# SUBBOARD-EMC_input.net
KiCad netlist of a schematic drawn in Altium Designer
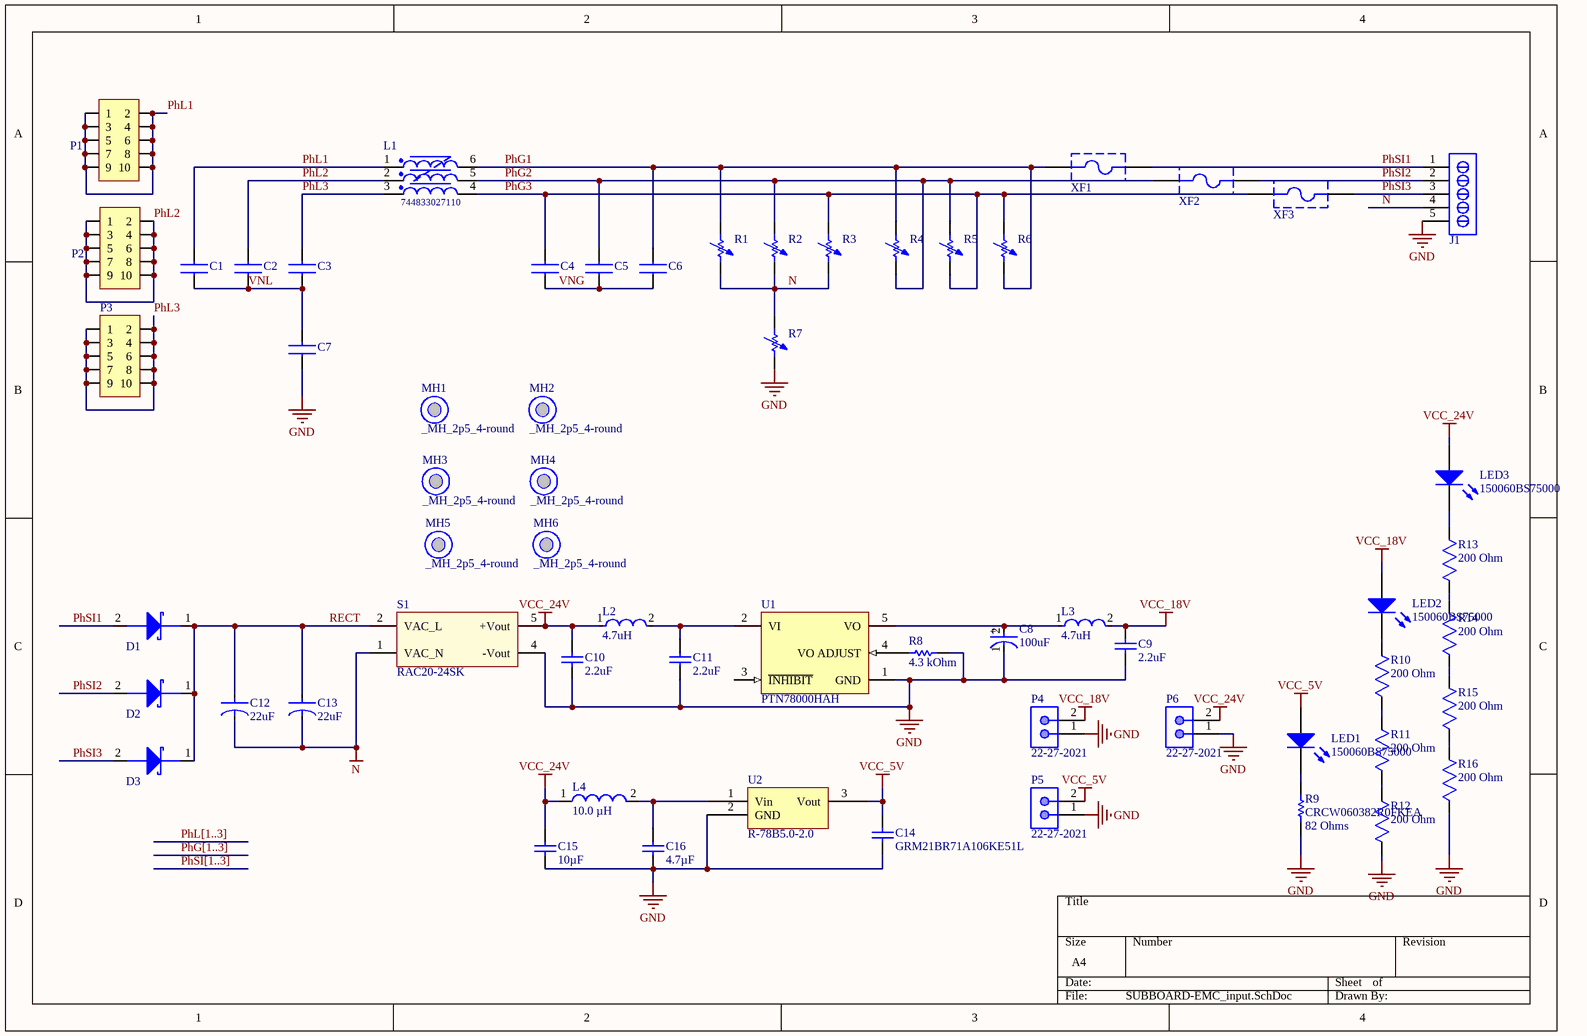
[diagram p0: SUBBOARD-EMC_input.SchDoc]

(export (version "E")
  (design (tool "Eeschema 10.0.6"))
  (components
    (comp (ref "C1")
      (value "PHE840MZ7100MF11R06L2")
      (footprint "PHE840MZ7100MF11R06L2")
      (description "CAP FILM 1UF 20% 760VDC RADIAL")
      (fields (field (name "MANUFACTURER") "KEMET") (field (name "TOLERANCE") "20%"))
      (libsource (lib "Altium_Library_POWERLAB") (part "PHE840MZ7100MF11R06L2"))
    )
    (comp (ref "C2")
      (value "PHE840MZ7100MF11R06L2")
      (footprint "PHE840MZ7100MF11R06L2")
      (description "CAP FILM 1UF 20% 760VDC RADIAL")
      (fields (field (name "MANUFACTURER") "KEMET") (field (name "TOLERANCE") "20%"))
      (libsource (lib "Altium_Library_POWERLAB") (part "PHE840MZ7100MF11R06L2"))
    )
    (comp (ref "C3")
      (value "PHE840MZ7100MF11R06L2")
      (footprint "PHE840MZ7100MF11R06L2")
      (description "CAP FILM 1UF 20% 760VDC RADIAL")
      (fields (field (name "MANUFACTURER") "KEMET") (field (name "TOLERANCE") "20%"))
      (libsource (lib "Altium_Library_POWERLAB") (part "PHE840MZ7100MF11R06L2"))
    )
    (comp (ref "C4")
      (value "PHE840MZ7100MF11R06L2")
      (footprint "PHE840MZ7100MF11R06L2")
      (description "CAP FILM 1UF 20% 760VDC RADIAL")
      (fields (field (name "MANUFACTURER") "KEMET") (field (name "TOLERANCE") "20%"))
      (libsource (lib "Altium_Library_POWERLAB") (part "PHE840MZ7100MF11R06L2"))
    )
    (comp (ref "C5")
      (value "PHE840MZ7100MF11R06L2")
      (footprint "PHE840MZ7100MF11R06L2")
      (description "CAP FILM 1UF 20% 760VDC RADIAL")
      (fields (field (name "MANUFACTURER") "KEMET") (field (name "TOLERANCE") "20%"))
      (libsource (lib "Altium_Library_POWERLAB") (part "PHE840MZ7100MF11R06L2"))
    )
    (comp (ref "C6")
      (value "PHE840MZ7100MF11R06L2")
      (footprint "PHE840MZ7100MF11R06L2")
      (description "CAP FILM 1UF 20% 760VDC RADIAL")
      (fields (field (name "MANUFACTURER") "KEMET") (field (name "TOLERANCE") "20%"))
      (libsource (lib "Altium_Library_POWERLAB") (part "PHE840MZ7100MF11R06L2"))
    )
    (comp (ref "C7")
      (value "PHE850ER7100MR03R06L2")
      (footprint "PHE850ER7100MR03R06L2")
      (description "CAP FILM 1UF 20% 1.25KVDC RADIAL")
      (fields (field (name "MANUFACTURER") "KEMET") (field (name "TOLERANCE") "20%"))
      (libsource (lib "Altium_Library_POWERLAB") (part "PHE850ER7100MR03R06L2"))
    )
    (comp (ref "C8")
      (value "EEE-FK1H101P")
      (footprint "FP-EEE-FK1H101P-MFG")
      (description "CAP ALUM 100UF 20% 50V SMD")
      (fields
        (field (name "TOLERANCE") "20%")
        (field (name "OCTOPART") "https://octopart.com/eeefk1h101p-panasonic-4642841")
        (field (name "CAPACITANCE") "100uF")
      )
      (libsource (lib "Altium Content Vault") (part "cf48714ba7e38822c1575c7ec0b6d1f"))
    )
    (comp (ref "C9")
      (value "C1210C225K5RACTU")
      (footprint "CAPC3225X140X50ML20T25")
      (description "Chip Capacitor, 2.2 uF, +/- 10%, 50 V, -55 to 125 degC, 1210 (3225 Metric), RoHS, Tape and Reel")
      (fields
        (field (name "MANUFACTURER") "Kemet")
        (field (name "CAPACITANCE") "2.2uF")
        (field (name "TOLERANCE") "10%")
      )
      (libsource (lib "Altium Content Vault") (part "CAP-NP-2"))
    )
    (comp (ref "C10")
      (value "C1210C225K5RACTU")
      (footprint "CAPC3225X140X50ML20T25")
      (description "Chip Capacitor, 2.2 uF, +/- 10%, 50 V, -55 to 125 degC, 1210 (3225 Metric), RoHS, Tape and Reel")
      (fields
        (field (name "MANUFACTURER") "Kemet")
        (field (name "CAPACITANCE") "2.2uF")
        (field (name "TOLERANCE") "10%")
      )
      (libsource (lib "Altium Content Vault") (part "CAP-NP-2"))
    )
    (comp (ref "C11")
      (value "C1210C225K5RACTU")
      (footprint "CAPC3225X140X50ML20T25")
      (description "Chip Capacitor, 2.2 uF, +/- 10%, 50 V, -55 to 125 degC, 1210 (3225 Metric), RoHS, Tape and Reel")
      (fields
        (field (name "MANUFACTURER") "Kemet")
        (field (name "CAPACITANCE") "2.2uF")
        (field (name "TOLERANCE") "10%")
      )
      (libsource (lib "Altium Content Vault") (part "CAP-NP-2"))
    )
    (comp (ref "C12")
      (value "EEV-EB2W220M")
      (footprint "EEV-EB2W220M")
      (description "CAP, ALU ELEC, 22UF, 450V, SMD")
      (fields
        (field (name "MANUFACTURER") "Panasonic")
        (field (name "CAPACITANCE") "22uF")
        (field (name "TOLERANCE") "20%")
      )
      (libsource (lib "Altium_Library_POWERLAB") (part "EEV-EB2W220M"))
    )
    (comp (ref "C13")
      (value "EEV-EB2W220M")
      (footprint "EEV-EB2W220M")
      (description "CAP, ALU ELEC, 22UF, 450V, SMD")
      (fields
        (field (name "MANUFACTURER") "Panasonic")
        (field (name "CAPACITANCE") "22uF")
        (field (name "TOLERANCE") "20%")
      )
      (libsource (lib "Altium_Library_POWERLAB") (part "EEV-EB2W220M"))
    )
    (comp (ref "C14")
      (value "GRM21BR71A106KE51L")
      (footprint "CAPC2013X140X45NL15T25")
      (fields (field (name "MANUFACTURER") "Murata"))
      (libsource (lib "Altium Content Vault") (part "CAP"))
    )
    (comp (ref "C15")
      (value "UMK325BJ106KM-T")
      (footprint "CAPC3225X270X60LL30T30")
      (description "Chip Capacitor, 10 uF, +/- 10%, 50 V, -55 to 85 degC, 1210 (3225 Metric), RoHS, Tape and Reel")
      (fields
        (field (name "TOLERANCE") "±10%")
        (field (name "CAPACITANCE") "10µF")
        (field (name "MANUFACTURER") "Taiyo Yuden")
      )
      (libsource (lib "Altium Content Vault") (part "CAP-NP-2"))
    )
    (comp (ref "C16")
      (value "UMK316AB7475KL-T")
      (footprint "CAPC3216X180X55LL20T30")
      (description "Chip Capacitor, 4.7 uF, +/- 10%, 50 V, -55 to 125 degC, 1206 (3216 Metric), RoHS, Tape and Reel")
      (fields
        (field (name "TOLERANCE") "±10%")
        (field (name "MANUFACTURER") "Taiyo Yuden")
        (field (name "CAPACITANCE") "4.7µF")
      )
      (libsource (lib "Altium Content Vault") (part "CAP-NP-2"))
    )
    (comp (ref "D1")
      (value "BYG23T-M3/TR")
      (footprint "BYG23T-M3/TR")
      (description "DIODE AVALANCHE 1300V 1A DO214AC")
      (fields (field (name "MANUFACTURER") "Vishay Semiconductors"))
      (libsource (lib "Altium_Library_POWERLAB") (part "BYG23T-M3/TR"))
    )
    (comp (ref "D2")
      (value "BYG23T-M3/TR")
      (footprint "BYG23T-M3/TR")
      (description "DIODE AVALANCHE 1300V 1A DO214AC")
      (fields (field (name "MANUFACTURER") "Vishay Semiconductors"))
      (libsource (lib "Altium_Library_POWERLAB") (part "BYG23T-M3/TR"))
    )
    (comp (ref "D3")
      (value "BYG23T-M3/TR")
      (footprint "BYG23T-M3/TR")
      (description "DIODE AVALANCHE 1300V 1A DO214AC")
      (fields (field (name "MANUFACTURER") "Vishay Semiconductors"))
      (libsource (lib "Altium_Library_POWERLAB") (part "BYG23T-M3/TR"))
    )
    (comp (ref "J1")
      (value "1715750")
      (footprint "SHDR5W110P0X500_1X5_2532X980X1380P")
      (description "Phoenix Contact MKDS 1.5/ 5-5.08, 5 Way PCB Terminal Block")
      (fields (field (name "MANUFACTURER") "Phoenix Contact") (field (name "VOLTAGE") "300V"))
      (libsource (lib "Altium_Library_POWERLAB") (part "1715750"))
    )
    (comp (ref "L1")
      (value "744833027110")
      (footprint "WE-TPB_Type 3XL_744833027110")
      (description "WE-TPB Common Mode Power Line Choke, Type 3XL, 2.7mH, 11A, 500V")
      (fields (field (name "MANUFACTURER") "Wurth Elektronik"))
      (libsource (lib "Altium_Library_POWERLAB") (part "744833027110"))
    )
    (comp (ref "L2")
      (value "IHLP1616BZER4R7M11")
      (footprint "FP-IHLP-1616BZ-FP_1_8545x-MFG")
      (description "Fixed Inductors Commercial Low DCR Series SMT 4.7uH 1.7A 105mΩ 20%")
      (fields (field (name "INDUCTANCE") "4.7uH") (field (name "TOLERANCE") "20%"))
      (libsource (lib "Altium Content Vault") (part "725321dda6339637d4d059423bc1c3c"))
    )
    (comp (ref "L3")
      (value "IHLP1616BZER4R7M11")
      (footprint "FP-IHLP-1616BZ-FP_1_8545x-MFG")
      (description "Fixed Inductors Commercial Low DCR Series SMT 4.7uH 1.7A 105mΩ 20%")
      (fields (field (name "INDUCTANCE") "4.7uH") (field (name "TOLERANCE") "20%"))
      (libsource (lib "Altium Content Vault") (part "725321dda6339637d4d059423bc1c3c"))
    )
    (comp (ref "L4")
      (value "744777910")
      (footprint "WE-PD-M-PB")
      (description "SMD-Shielded Power Inductor WE-PD, L = 10.0 µH")
      (fields (field (name "INDUCTANCE") "10.0 µH"))
      (libsource (lib "Altium Content Vault") (part "PAS-IND-INDUCTOR-2"))
    )
    (comp (ref "LED1")
      (value "150060BS75000")
      (footprint "0603_A")
      (description "SMD mono-color Chip LED, WL-SMCW, Blue")
      (fields (field (name "MANUFACTURER") "Wuerth Elektronik"))
      (libsource (lib "Altium Content Vault") (part "WE-LED_K1A2-2"))
    )
    (comp (ref "LED2")
      (value "150060BS75000")
      (footprint "0603_A")
      (description "SMD mono-color Chip LED, WL-SMCW, Blue")
      (fields (field (name "MANUFACTURER") "Wuerth Elektronik"))
      (libsource (lib "Altium Content Vault") (part "WE-LED_K1A2-2"))
    )
    (comp (ref "LED3")
      (value "150060BS75000")
      (footprint "0603_A")
      (description "SMD mono-color Chip LED, WL-SMCW, Blue")
      (fields (field (name "MANUFACTURER") "Wuerth Elektronik"))
      (libsource (lib "Altium Content Vault") (part "WE-LED_K1A2-2"))
    )
    (comp (ref "MH1")
      (value "_MH_2p5_4-round")
      (footprint "_MH_2p5_4-round")
      (description "matching hole 2.5 hole, 4mm pad (round)")
      (libsource (lib "Altium_Library_POWERLAB") (part "_MH_2p5_4-round"))
    )
    (comp (ref "MH2")
      (value "_MH_2p5_4-round")
      (footprint "_MH_2p5_4-round")
      (description "matching hole 2.5 hole, 4mm pad (round)")
      (libsource (lib "Altium_Library_POWERLAB") (part "_MH_2p5_4-round"))
    )
    (comp (ref "MH3")
      (value "_MH_2p5_4-round")
      (footprint "_MH_2p5_4-round")
      (description "matching hole 2.5 hole, 4mm pad (round)")
      (libsource (lib "Altium_Library_POWERLAB") (part "_MH_2p5_4-round"))
    )
    (comp (ref "MH4")
      (value "_MH_2p5_4-round")
      (footprint "_MH_2p5_4-round")
      (description "matching hole 2.5 hole, 4mm pad (round)")
      (libsource (lib "Altium_Library_POWERLAB") (part "_MH_2p5_4-round"))
    )
    (comp (ref "MH5")
      (value "_MH_2p5_4-round")
      (footprint "_MH_2p5_4-round")
      (description "matching hole 2.5 hole, 4mm pad (round)")
      (libsource (lib "Altium_Library_POWERLAB") (part "_MH_2p5_4-round"))
    )
    (comp (ref "MH6")
      (value "_MH_2p5_4-round")
      (footprint "_MH_2p5_4-round")
      (description "matching hole 2.5 hole, 4mm pad (round)")
      (libsource (lib "Altium_Library_POWERLAB") (part "_MH_2p5_4-round"))
    )
    (comp (ref "P1")
      (value "IPT1-105-01-S-D-RA")
      (footprint "IPT1-105-01-S-D-RA")
      (description "CONN PLUG .100\" 10POS DL PCB R/A")
      (fields (field (name "MANUFACTURER") "Samtec"))
      (libsource (lib "Altium_Library_POWERLAB") (part "IPT1-105-01-S-D-RA"))
    )
    (comp (ref "P2")
      (value "IPT1-105-01-S-D-RA")
      (footprint "IPT1-105-01-S-D-RA")
      (description "CONN PLUG .100\" 10POS DL PCB R/A")
      (fields (field (name "MANUFACTURER") "Samtec"))
      (libsource (lib "Altium_Library_POWERLAB") (part "IPT1-105-01-S-D-RA"))
    )
    (comp (ref "P3")
      (value "IPT1-105-01-S-D-RA")
      (footprint "IPT1-105-01-S-D-RA")
      (description "CONN PLUG .100\" 10POS DL PCB R/A")
      (fields (field (name "MANUFACTURER") "Samtec"))
      (libsource (lib "Altium_Library_POWERLAB") (part "IPT1-105-01-S-D-RA"))
    )
    (comp (ref "P4")
      (value "22-27-2021")
      (footprint "MOLX-22-27-2021_V")
      (fields (field (name "MANUFACTURER") "Molex") (field (name "PARTNUMBER") "0022272021"))
      (libsource (lib "Altium Content Vault") (part "CN-1P-M-R2"))
    )
    (comp (ref "P5")
      (value "22-27-2021")
      (footprint "MOLX-22-27-2021_V")
      (fields (field (name "MANUFACTURER") "Molex") (field (name "PARTNUMBER") "0022272021"))
      (libsource (lib "Altium Content Vault") (part "CN-1P-M-R2"))
    )
    (comp (ref "P6")
      (value "22-27-2021")
      (footprint "MOLX-22-27-2021_V")
      (fields (field (name "MANUFACTURER") "Molex") (field (name "PARTNUMBER") "0022272021"))
      (libsource (lib "Altium Content Vault") (part "CN-1P-M-R2"))
    )
    (comp (ref "R1")
      (value "VDRS07H300BSE")
      (footprint "VISH-VDRS07-53x22-2_V")
      (fields (field (name "MANUFACTURER") "Vishay Semiconductor"))
      (libsource (lib "Altium Content Vault") (part "VISH-RES_VAR-2"))
    )
    (comp (ref "R2")
      (value "VDRS07H300BSE")
      (footprint "VISH-VDRS07-53x22-2_V")
      (fields (field (name "MANUFACTURER") "Vishay Semiconductor"))
      (libsource (lib "Altium Content Vault") (part "VISH-RES_VAR-2"))
    )
    (comp (ref "R3")
      (value "VDRS07H300BSE")
      (footprint "VISH-VDRS07-53x22-2_V")
      (fields (field (name "MANUFACTURER") "Vishay Semiconductor"))
      (libsource (lib "Altium Content Vault") (part "VISH-RES_VAR-2"))
    )
    (comp (ref "R4")
      (value "VDRS07H300BSE")
      (footprint "VISH-VDRS07-53x22-2_V")
      (fields (field (name "MANUFACTURER") "Vishay Semiconductor"))
      (libsource (lib "Altium Content Vault") (part "VISH-RES_VAR-2"))
    )
    (comp (ref "R5")
      (value "VDRS07H300BSE")
      (footprint "VISH-VDRS07-53x22-2_V")
      (fields (field (name "MANUFACTURER") "Vishay Semiconductor"))
      (libsource (lib "Altium Content Vault") (part "VISH-RES_VAR-2"))
    )
    (comp (ref "R6")
      (value "VDRS07H300BSE")
      (footprint "VISH-VDRS07-53x22-2_V")
      (fields (field (name "MANUFACTURER") "Vishay Semiconductor"))
      (libsource (lib "Altium Content Vault") (part "VISH-RES_VAR-2"))
    )
    (comp (ref "R7")
      (value "VDRS07H300BSE")
      (footprint "VISH-VDRS07-53x22-2_V")
      (fields (field (name "MANUFACTURER") "Vishay Semiconductor"))
      (libsource (lib "Altium Content Vault") (part "VISH-RES_VAR-2"))
    )
    (comp (ref "R8")
      (value "4.3 kOhm")
      (footprint "RESC2013X60X40LL20T25")
      (fields (field (name "MANUFACTURER") "Panasonic") (field (name "PART NUMBER") "ERA6AEB432V"))
      (libsource (lib "Altium Content Vault") (part "RES"))
    )
    (comp (ref "R9")
      (value "CRCW060382R0FKEA")
      (footprint "RESC1609X50X30LL10T20")
      (fields (field (name "MANUFACTURER") "Vishay Dale") (field (name "ALTIUM_VALUE") "82 Ohms"))
      (libsource (lib "Altium Content Vault") (part "RES"))
    )
    (comp (ref "R10")
      (value "200 Ohm")
      (footprint "CRCW0603200RFKEAHP")
      (description "CRCW0603200RFKEAHP\r\nRes Thick Film 0603 200 Ohm 1% 0.25W(1/4W) ±100ppm/C Pad SMD Automotive T/R")
      (fields
        (field (name "MANUFACTURER") "Vishay Dale")
        (field (name "MANUFACTURER PART NUMBER") "CRCW0603200RFKEAHP")
      )
      (libsource (lib "Altium_Library_POWERLAB") (part "CRCW0603200RFKEAHP"))
    )
    (comp (ref "R11")
      (value "200 Ohm")
      (footprint "CRCW0603200RFKEAHP")
      (description "CRCW0603200RFKEAHP\r\nRes Thick Film 0603 200 Ohm 1% 0.25W(1/4W) ±100ppm/C Pad SMD Automotive T/R")
      (fields
        (field (name "MANUFACTURER") "Vishay Dale")
        (field (name "MANUFACTURER PART NUMBER") "CRCW0603200RFKEAHP")
      )
      (libsource (lib "Altium_Library_POWERLAB") (part "CRCW0603200RFKEAHP"))
    )
    (comp (ref "R12")
      (value "200 Ohm")
      (footprint "CRCW0603200RFKEAHP")
      (description "CRCW0603200RFKEAHP\r\nRes Thick Film 0603 200 Ohm 1% 0.25W(1/4W) ±100ppm/C Pad SMD Automotive T/R")
      (fields
        (field (name "MANUFACTURER") "Vishay Dale")
        (field (name "MANUFACTURER PART NUMBER") "CRCW0603200RFKEAHP")
      )
      (libsource (lib "Altium_Library_POWERLAB") (part "CRCW0603200RFKEAHP"))
    )
    (comp (ref "R13")
      (value "200 Ohm")
      (footprint "CRCW0603200RFKEAHP")
      (description "CRCW0603200RFKEAHP\r\nRes Thick Film 0603 200 Ohm 1% 0.25W(1/4W) ±100ppm/C Pad SMD Automotive T/R")
      (fields
        (field (name "MANUFACTURER") "Vishay Dale")
        (field (name "MANUFACTURER PART NUMBER") "CRCW0603200RFKEAHP")
      )
      (libsource (lib "Altium_Library_POWERLAB") (part "CRCW0603200RFKEAHP"))
    )
    (comp (ref "R14")
      (value "200 Ohm")
      (footprint "CRCW0603200RFKEAHP")
      (description "CRCW0603200RFKEAHP\r\nRes Thick Film 0603 200 Ohm 1% 0.25W(1/4W) ±100ppm/C Pad SMD Automotive T/R")
      (fields
        (field (name "MANUFACTURER") "Vishay Dale")
        (field (name "MANUFACTURER PART NUMBER") "CRCW0603200RFKEAHP")
      )
      (libsource (lib "Altium_Library_POWERLAB") (part "CRCW0603200RFKEAHP"))
    )
    (comp (ref "R15")
      (value "200 Ohm")
      (footprint "CRCW0603200RFKEAHP")
      (description "CRCW0603200RFKEAHP\r\nRes Thick Film 0603 200 Ohm 1% 0.25W(1/4W) ±100ppm/C Pad SMD Automotive T/R")
      (fields
        (field (name "MANUFACTURER") "Vishay Dale")
        (field (name "MANUFACTURER PART NUMBER") "CRCW0603200RFKEAHP")
      )
      (libsource (lib "Altium_Library_POWERLAB") (part "CRCW0603200RFKEAHP"))
    )
    (comp (ref "R16")
      (value "200 Ohm")
      (footprint "CRCW0603200RFKEAHP")
      (description "CRCW0603200RFKEAHP\r\nRes Thick Film 0603 200 Ohm 1% 0.25W(1/4W) ±100ppm/C Pad SMD Automotive T/R")
      (fields
        (field (name "MANUFACTURER") "Vishay Dale")
        (field (name "MANUFACTURER PART NUMBER") "CRCW0603200RFKEAHP")
      )
      (libsource (lib "Altium_Library_POWERLAB") (part "CRCW0603200RFKEAHP"))
    )
    (comp (ref "S1")
      (value "RAC20-24SK")
      (footprint "RAC20-K")
      (description "20 Watt 2'' x 1'' Single output 24VDC Regulated SMPS RAC20-24SK")
      (libsource (lib "Altium_Library_POWERLAB") (part "RAC20-24SK"))
    )
    (comp (ref "U1")
      (value "PTN78000HAH")
      (footprint "EUS0005A")
      (description "1.5 A, Wide Input, Wide Output Adjust Module, -40 to 85 degC, 5-pin Module (EUS5), Pb-Free (RoHS)")
      (fields (field (name "MANUFACTURER") "Texas Instruments"))
      (libsource (lib "Altium Content Vault") (part "TI-PTN78000HEUS5"))
    )
    (comp (ref "U2")
      (value "R-78B5.0-2.0")
      (footprint "R-78B5.0-2.0")
      (description "DC DC CONVERTER 5V")
      (fields (field (name "MANUFACTURER") "Recom"))
      (libsource (lib "Altium_Library_POWERLAB") (part "R-78B5.0-2.0"))
    )
    (comp (ref "XF1")
      (value "696108003002")
      (footprint "696108003002")
      (description "FUSEHOLDER BLOCKS - PCB - CLIP C")
      (fields (field (name "MANUFACTURER") "Wurth Electronics") (field (name "VOLTAGE") "250V"))
      (libsource (lib "Altium_Library_POWERLAB") (part "696108003002"))
    )
    (comp (ref "XF2")
      (value "696108003002")
      (footprint "696108003002")
      (description "FUSEHOLDER BLOCKS - PCB - CLIP C")
      (fields (field (name "MANUFACTURER") "Wurth Electronics") (field (name "VOLTAGE") "250V"))
      (libsource (lib "Altium_Library_POWERLAB") (part "696108003002"))
    )
    (comp (ref "XF3")
      (value "696108003002")
      (footprint "696108003002")
      (description "FUSEHOLDER BLOCKS - PCB - CLIP C")
      (fields (field (name "MANUFACTURER") "Wurth Electronics") (field (name "VOLTAGE") "250V"))
      (libsource (lib "Altium_Library_POWERLAB") (part "696108003002"))
    )
  )
  (nets
    (net (code "1") (name "/PhG1") (class "Default")
      (node (ref "C6") (pin "1") (pinfunction "1_1") (pintype "passive"))
      (node (ref "L1") (pin "6") (pinfunction "6_6") (pintype "passive"))
      (node (ref "R1") (pin "1") (pinfunction "1_1") (pintype "passive"))
      (node (ref "R4") (pin "1") (pinfunction "1_1") (pintype "passive"))
      (node (ref "R6") (pin "2") (pinfunction "2_2") (pintype "passive"))
      (node (ref "XF1") (pin "1") (pinfunction "1_1") (pintype "passive"))
    )
    (net (code "2") (name "/PhG2") (class "Default")
      (node (ref "C5") (pin "1") (pinfunction "1_1") (pintype "passive"))
      (node (ref "L1") (pin "5") (pinfunction "5_5") (pintype "passive"))
      (node (ref "R2") (pin "1") (pinfunction "1_1") (pintype "passive"))
      (node (ref "R4") (pin "2") (pinfunction "2_2") (pintype "passive"))
      (node (ref "R5") (pin "1") (pinfunction "1_1") (pintype "passive"))
      (node (ref "XF2") (pin "1") (pinfunction "1_1") (pintype "passive"))
    )
    (net (code "3") (name "/PhG3") (class "Default")
      (node (ref "C4") (pin "1") (pinfunction "1_1") (pintype "passive"))
      (node (ref "L1") (pin "4") (pinfunction "4_4") (pintype "passive"))
      (node (ref "R3") (pin "1") (pinfunction "1_1") (pintype "passive"))
      (node (ref "R5") (pin "2") (pinfunction "2_2") (pintype "passive"))
      (node (ref "R6") (pin "1") (pinfunction "1_1") (pintype "passive"))
      (node (ref "XF3") (pin "1") (pinfunction "1_1") (pintype "passive"))
    )
    (net (code "5") (name "/PhL1") (class "Default")
      (node (ref "C1") (pin "1") (pinfunction "1_1") (pintype "passive"))
      (node (ref "L1") (pin "1") (pinfunction "1_1") (pintype "passive"))
      (node (ref "P1") (pin "1") (pinfunction "1_1") (pintype "passive"))
      (node (ref "P1") (pin "10") (pinfunction "10_10") (pintype "passive"))
      (node (ref "P1") (pin "2") (pinfunction "2_2") (pintype "passive"))
      (node (ref "P1") (pin "3") (pinfunction "3_3") (pintype "passive"))
      (node (ref "P1") (pin "4") (pinfunction "4_4") (pintype "passive"))
      (node (ref "P1") (pin "5") (pinfunction "5_5") (pintype "passive"))
      (node (ref "P1") (pin "6") (pinfunction "6_6") (pintype "passive"))
      (node (ref "P1") (pin "7") (pinfunction "7_7") (pintype "passive"))
      (node (ref "P1") (pin "8") (pinfunction "8_8") (pintype "passive"))
      (node (ref "P1") (pin "9") (pinfunction "9_9") (pintype "passive"))
    )
    (net (code "6") (name "/PhL2") (class "Default")
      (node (ref "C2") (pin "1") (pinfunction "1_1") (pintype "passive"))
      (node (ref "L1") (pin "2") (pinfunction "2_2") (pintype "passive"))
      (node (ref "P2") (pin "1") (pinfunction "1_1") (pintype "passive"))
      (node (ref "P2") (pin "10") (pinfunction "10_10") (pintype "passive"))
      (node (ref "P2") (pin "2") (pinfunction "2_2") (pintype "passive"))
      (node (ref "P2") (pin "3") (pinfunction "3_3") (pintype "passive"))
      (node (ref "P2") (pin "4") (pinfunction "4_4") (pintype "passive"))
      (node (ref "P2") (pin "5") (pinfunction "5_5") (pintype "passive"))
      (node (ref "P2") (pin "6") (pinfunction "6_6") (pintype "passive"))
      (node (ref "P2") (pin "7") (pinfunction "7_7") (pintype "passive"))
      (node (ref "P2") (pin "8") (pinfunction "8_8") (pintype "passive"))
      (node (ref "P2") (pin "9") (pinfunction "9_9") (pintype "passive"))
    )
    (net (code "7") (name "/PhL3") (class "Default")
      (node (ref "C3") (pin "1") (pinfunction "1_1") (pintype "passive"))
      (node (ref "L1") (pin "3") (pinfunction "3_3") (pintype "passive"))
      (node (ref "P3") (pin "1") (pinfunction "1_1") (pintype "passive"))
      (node (ref "P3") (pin "10") (pinfunction "10_10") (pintype "passive"))
      (node (ref "P3") (pin "2") (pinfunction "2_2") (pintype "passive"))
      (node (ref "P3") (pin "3") (pinfunction "3_3") (pintype "passive"))
      (node (ref "P3") (pin "4") (pinfunction "4_4") (pintype "passive"))
      (node (ref "P3") (pin "5") (pinfunction "5_5") (pintype "passive"))
      (node (ref "P3") (pin "6") (pinfunction "6_6") (pintype "passive"))
      (node (ref "P3") (pin "7") (pinfunction "7_7") (pintype "passive"))
      (node (ref "P3") (pin "8") (pinfunction "8_8") (pintype "passive"))
      (node (ref "P3") (pin "9") (pinfunction "9_9") (pintype "passive"))
    )
    (net (code "9") (name "/PhSI1") (class "Default")
      (node (ref "D1") (pin "2") (pinfunction "Anode_2") (pintype "passive"))
      (node (ref "J1") (pin "1") (pinfunction "1_1") (pintype "passive"))
      (node (ref "XF1") (pin "2") (pinfunction "2_2") (pintype "passive"))
    )
    (net (code "10") (name "/PhSI2") (class "Default")
      (node (ref "D2") (pin "2") (pinfunction "Anode_2") (pintype "passive"))
      (node (ref "J1") (pin "2") (pinfunction "2_2") (pintype "passive"))
      (node (ref "XF2") (pin "2") (pinfunction "2_2") (pintype "passive"))
    )
    (net (code "11") (name "/PhSI3") (class "Default")
      (node (ref "D3") (pin "2") (pinfunction "Anode_2") (pintype "passive"))
      (node (ref "J1") (pin "3") (pinfunction "3_3") (pintype "passive"))
      (node (ref "XF3") (pin "2") (pinfunction "2_2") (pintype "passive"))
    )
    (net (code "13") (name "/RECT") (class "Default")
      (node (ref "C12") (pin "1") (pinfunction "1_1") (pintype "passive"))
      (node (ref "C13") (pin "1") (pinfunction "1_1") (pintype "passive"))
      (node (ref "D1") (pin "1") (pinfunction "Cathode_1") (pintype "passive"))
      (node (ref "D2") (pin "1") (pinfunction "Cathode_1") (pintype "passive"))
      (node (ref "D3") (pin "1") (pinfunction "Cathode_1") (pintype "passive"))
      (node (ref "S1") (pin "2") (pinfunction "VAC_L_2") (pintype "passive"))
    )
    (net (code "14") (name "/VNG") (class "Default")
      (node (ref "C4") (pin "2") (pinfunction "2_2") (pintype "passive"))
      (node (ref "C5") (pin "2") (pinfunction "2_2") (pintype "passive"))
      (node (ref "C6") (pin "2") (pinfunction "2_2") (pintype "passive"))
    )
    (net (code "15") (name "/VNL") (class "Default")
      (node (ref "C1") (pin "2") (pinfunction "2_2") (pintype "passive"))
      (node (ref "C2") (pin "2") (pinfunction "2_2") (pintype "passive"))
      (node (ref "C3") (pin "2") (pinfunction "2_2") (pintype "passive"))
      (node (ref "C7") (pin "1") (pinfunction "1_1") (pintype "passive"))
    )
    (net (code "16") (name "GND") (class "Default")
      (node (ref "C10") (pin "2") (pinfunction "2_2") (pintype "passive"))
      (node (ref "C11") (pin "2") (pinfunction "2_2") (pintype "passive"))
      (node (ref "C14") (pin "1") (pinfunction "1_1") (pintype "passive"))
      (node (ref "C15") (pin "2") (pinfunction "2_2") (pintype "passive"))
      (node (ref "C16") (pin "2") (pinfunction "2_2") (pintype "passive"))
      (node (ref "C7") (pin "2") (pinfunction "2_2") (pintype "passive"))
      (node (ref "C8") (pin "1") (pinfunction "C_1") (pintype "passive"))
      (node (ref "C9") (pin "2") (pinfunction "2_2") (pintype "passive"))
      (node (ref "J1") (pin "5") (pinfunction "5_5") (pintype "passive"))
      (node (ref "P4") (pin "1") (pinfunction "1_1") (pintype "passive"))
      (node (ref "P5") (pin "1") (pinfunction "1_1") (pintype "passive"))
      (node (ref "P6") (pin "1") (pinfunction "1_1") (pintype "passive"))
      (node (ref "R12") (pin "1") (pinfunction "1_1") (pintype "passive"))
      (node (ref "R16") (pin "1") (pinfunction "1_1") (pintype "passive"))
      (node (ref "R7") (pin "2") (pinfunction "2_2") (pintype "passive"))
      (node (ref "R8") (pin "1") (pinfunction "1_1") (pintype "passive"))
      (node (ref "R9") (pin "2") (pinfunction "2_2") (pintype "passive"))
      (node (ref "S1") (pin "4") (pinfunction "-Vout_4") (pintype "passive"))
      (node (ref "U1") (pin "1") (pinfunction "GND_1") (pintype "power_in"))
      (node (ref "U2") (pin "2") (pinfunction "GND_2") (pintype "passive"))
    )
    (net (code "17") (name "N") (class "Default")
      (node (ref "C12") (pin "2") (pinfunction "2_2") (pintype "passive"))
      (node (ref "C13") (pin "2") (pinfunction "2_2") (pintype "passive"))
      (node (ref "J1") (pin "4") (pinfunction "4_4") (pintype "passive"))
      (node (ref "R1") (pin "2") (pinfunction "2_2") (pintype "passive"))
      (node (ref "R2") (pin "2") (pinfunction "2_2") (pintype "passive"))
      (node (ref "R3") (pin "2") (pinfunction "2_2") (pintype "passive"))
      (node (ref "R7") (pin "1") (pinfunction "1_1") (pintype "passive"))
      (node (ref "S1") (pin "1") (pinfunction "VAC_N_1") (pintype "passive"))
    )
    (net (code "18") (name "Net-(C8-A)") (class "Default")
      (node (ref "C8") (pin "2") (pinfunction "A_2") (pintype "passive"))
      (node (ref "L3") (pin "1") (pinfunction "1_1") (pintype "passive"))
      (node (ref "U1") (pin "5") (pinfunction "VO_5") (pintype "power_in"))
    )
    (net (code "19") (name "Net-(LED1-K)") (class "Default")
      (node (ref "LED1") (pin "1") (pinfunction "K_1") (pintype "passive"))
      (node (ref "R9") (pin "1") (pinfunction "1_1") (pintype "passive"))
    )
    (net (code "20") (name "Net-(LED2-K)") (class "Default")
      (node (ref "LED2") (pin "1") (pinfunction "K_1") (pintype "passive"))
      (node (ref "R10") (pin "2") (pinfunction "2_2") (pintype "passive"))
    )
    (net (code "21") (name "Net-(LED3-K)") (class "Default")
      (node (ref "LED3") (pin "1") (pinfunction "K_1") (pintype "passive"))
      (node (ref "R13") (pin "2") (pinfunction "2_2") (pintype "passive"))
    )
    (net (code "22") (name "Net-(R10-Pad1)") (class "Default")
      (node (ref "R10") (pin "1") (pinfunction "1_1") (pintype "passive"))
      (node (ref "R11") (pin "2") (pinfunction "2_2") (pintype "passive"))
    )
    (net (code "23") (name "Net-(R11-Pad1)") (class "Default")
      (node (ref "R11") (pin "1") (pinfunction "1_1") (pintype "passive"))
      (node (ref "R12") (pin "2") (pinfunction "2_2") (pintype "passive"))
    )
    (net (code "24") (name "Net-(R13-Pad1)") (class "Default")
      (node (ref "R13") (pin "1") (pinfunction "1_1") (pintype "passive"))
      (node (ref "R14") (pin "2") (pinfunction "2_2") (pintype "passive"))
    )
    (net (code "25") (name "Net-(R14-Pad1)") (class "Default")
      (node (ref "R14") (pin "1") (pinfunction "1_1") (pintype "passive"))
      (node (ref "R15") (pin "1") (pinfunction "1_1") (pintype "passive"))
    )
    (net (code "26") (name "Net-(R15-Pad2)") (class "Default")
      (node (ref "R15") (pin "2") (pinfunction "2_2") (pintype "passive"))
      (node (ref "R16") (pin "2") (pinfunction "2_2") (pintype "passive"))
    )
    (net (code "27") (name "Net-(U1-VI)") (class "Default")
      (node (ref "C11") (pin "1") (pinfunction "1_1") (pintype "passive"))
      (node (ref "L2") (pin "2") (pinfunction "2_2") (pintype "passive"))
      (node (ref "U1") (pin "2") (pinfunction "VI_2") (pintype "power_in"))
    )
    (net (code "28") (name "Net-(U1-VO_ADJUST)") (class "Default")
      (node (ref "R8") (pin "2") (pinfunction "2_2") (pintype "passive"))
      (node (ref "U1") (pin "4") (pinfunction "VO_ADJUST_4") (pintype "input"))
    )
    (net (code "29") (name "Net-(U2-Vin)") (class "Default")
      (node (ref "C16") (pin "1") (pinfunction "1_1") (pintype "passive"))
      (node (ref "L4") (pin "2") (pinfunction "2_2") (pintype "passive"))
      (node (ref "U2") (pin "1") (pinfunction "Vin_1") (pintype "passive"))
    )
    (net (code "30") (name "VCC_5V") (class "Default")
      (node (ref "C14") (pin "2") (pinfunction "2_2") (pintype "passive"))
      (node (ref "LED1") (pin "2") (pinfunction "A_2") (pintype "passive"))
      (node (ref "P5") (pin "2") (pinfunction "2_2") (pintype "passive"))
      (node (ref "U2") (pin "3") (pinfunction "Vout_3") (pintype "passive"))
    )
    (net (code "31") (name "VCC_18V") (class "Default")
      (node (ref "C9") (pin "1") (pinfunction "1_1") (pintype "passive"))
      (node (ref "L3") (pin "2") (pinfunction "2_2") (pintype "passive"))
      (node (ref "LED2") (pin "2") (pinfunction "A_2") (pintype "passive"))
      (node (ref "P4") (pin "2") (pinfunction "2_2") (pintype "passive"))
    )
    (net (code "32") (name "VCC_24V") (class "Default")
      (node (ref "C10") (pin "1") (pinfunction "1_1") (pintype "passive"))
      (node (ref "C15") (pin "1") (pinfunction "1_1") (pintype "passive"))
      (node (ref "L2") (pin "1") (pinfunction "1_1") (pintype "passive"))
      (node (ref "L4") (pin "1") (pinfunction "1_1") (pintype "passive"))
      (node (ref "LED3") (pin "2") (pinfunction "A_2") (pintype "passive"))
      (node (ref "P6") (pin "2") (pinfunction "2_2") (pintype "passive"))
      (node (ref "S1") (pin "5") (pinfunction "+Vout_5") (pintype "passive"))
    )
    (net (code "33") (name "unconnected-(U1-~{INHIBIT}-Pad3)") (class "Default")
      (node (ref "U1") (pin "3") (pinfunction "~{INHIBIT}_3") (pintype "input"))
    )
  )
)
